# CarTalkImu.net
KiCad netlist of a schematic drawn in EAGLE
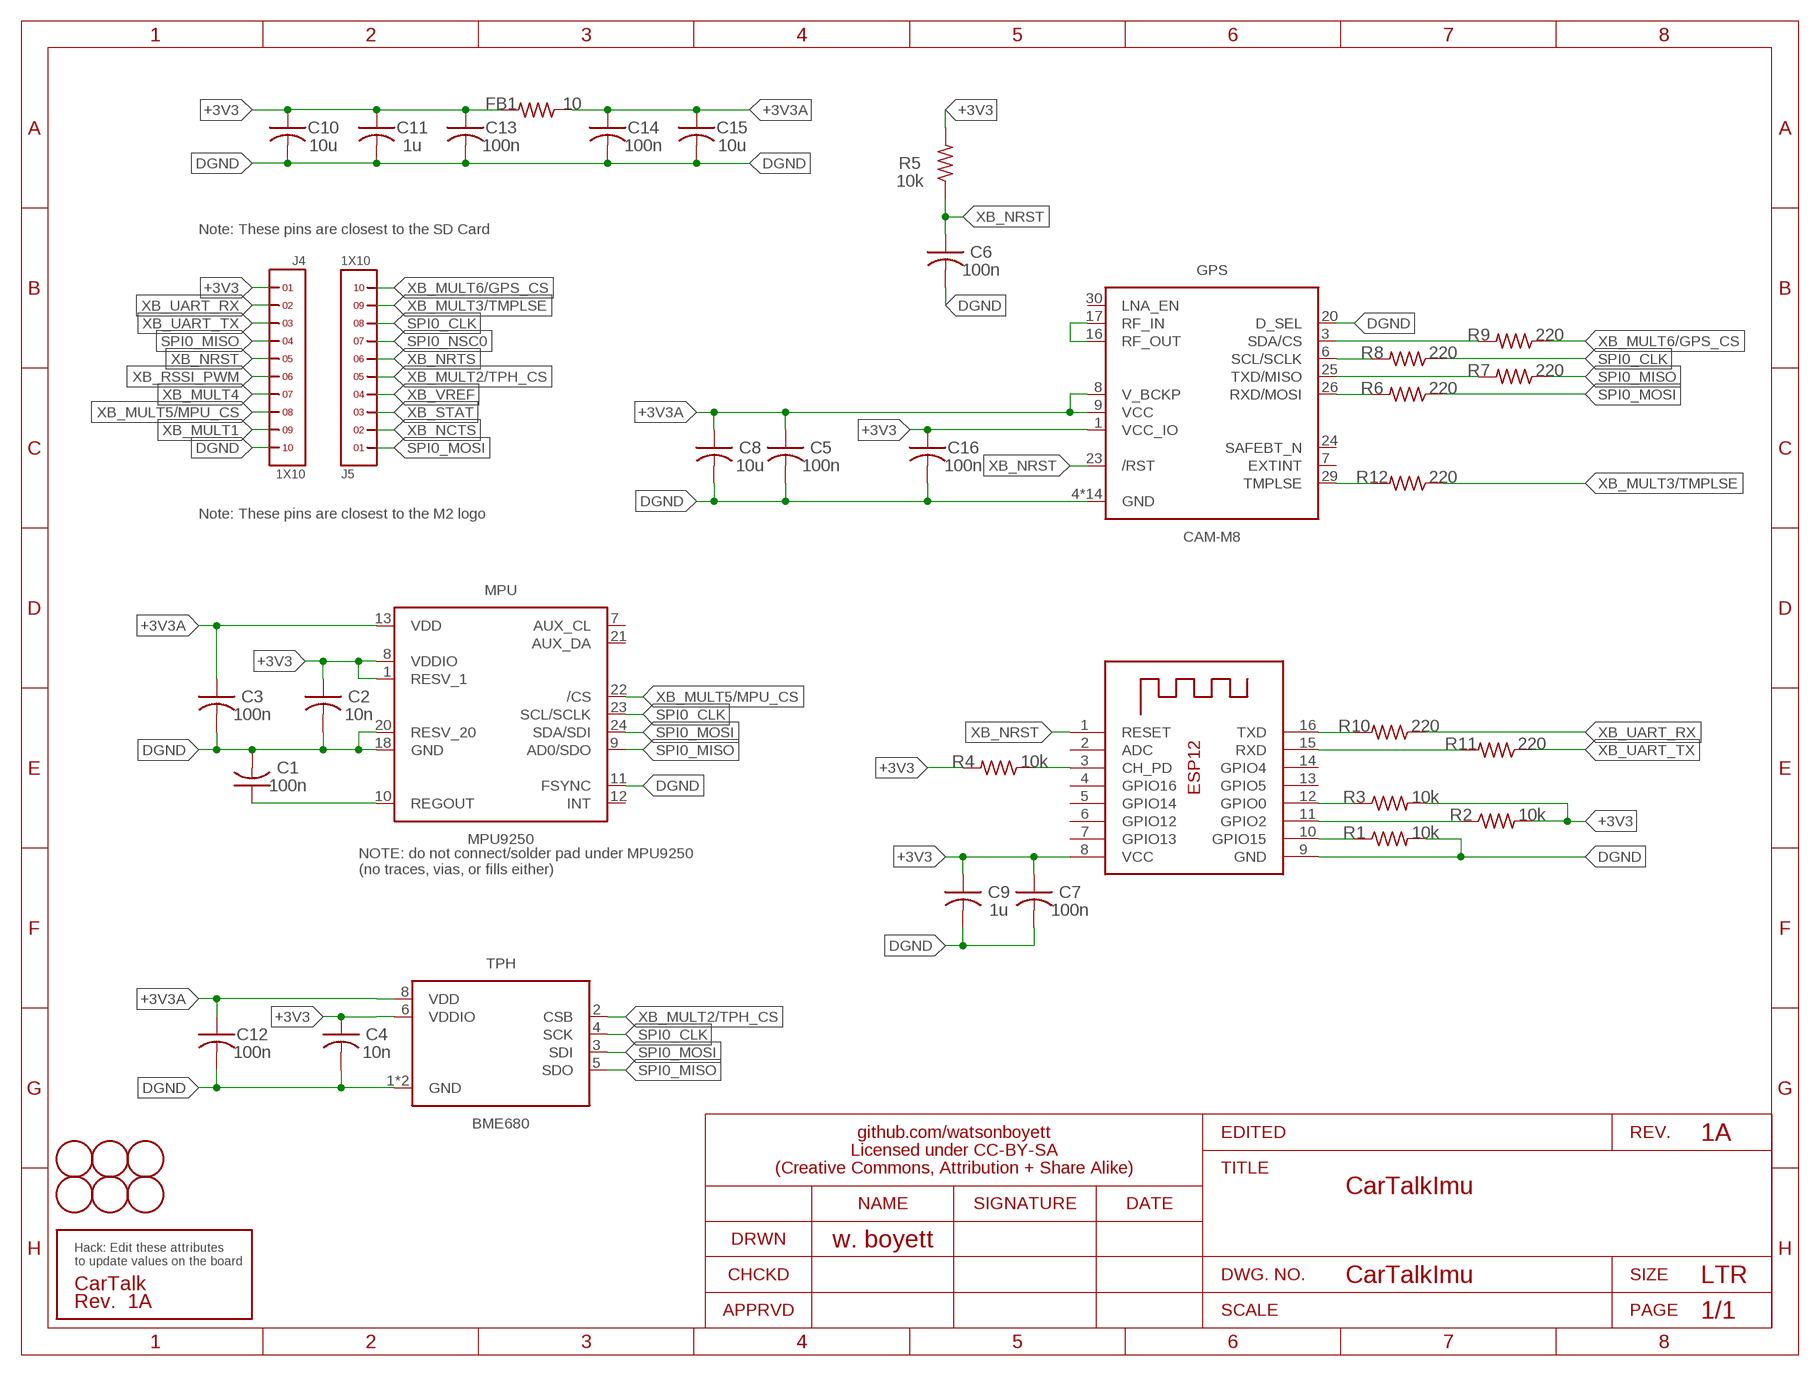
[diagram p0: schematic, sheet 1]

(export (version "E")
  (design (tool "Eeschema 10.0.6"))
  (components
    (comp (ref "C1")
      (value "100n")
      (footprint "eagle-import:C0603")
      (libsource (lib "eagle-import") (part "C-USC0603"))
    )
    (comp (ref "C2")
      (value "10n")
      (footprint "eagle-import:C0603")
      (libsource (lib "eagle-import") (part "C-USC0603"))
    )
    (comp (ref "C3")
      (value "100n")
      (footprint "eagle-import:C0603")
      (libsource (lib "eagle-import") (part "C-USC0603"))
    )
    (comp (ref "C4")
      (value "10n")
      (footprint "eagle-import:C0603")
      (libsource (lib "eagle-import") (part "C-USC0603"))
    )
    (comp (ref "C5")
      (value "100n")
      (footprint "eagle-import:C0603")
      (libsource (lib "eagle-import") (part "C-USC0603"))
    )
    (comp (ref "C6")
      (value "100n")
      (footprint "eagle-import:C0603")
      (libsource (lib "eagle-import") (part "C-USC0603"))
    )
    (comp (ref "C7")
      (value "100n")
      (footprint "eagle-import:C0603")
      (libsource (lib "eagle-import") (part "C-USC0603"))
    )
    (comp (ref "C8")
      (value "10u")
      (footprint "eagle-import:C0805")
      (libsource (lib "eagle-import") (part "C-USC0805"))
    )
    (comp (ref "C9")
      (value "1u")
      (footprint "eagle-import:C0603")
      (libsource (lib "eagle-import") (part "C-USC0603"))
    )
    (comp (ref "C10")
      (value "10u")
      (footprint "eagle-import:C0805")
      (libsource (lib "eagle-import") (part "C-USC0805"))
    )
    (comp (ref "C11")
      (value "1u")
      (footprint "eagle-import:C0603")
      (libsource (lib "eagle-import") (part "C-USC0603"))
    )
    (comp (ref "C12")
      (value "100n")
      (footprint "eagle-import:C0603")
      (libsource (lib "eagle-import") (part "C-USC0603"))
    )
    (comp (ref "C13")
      (value "100n")
      (footprint "eagle-import:C0603")
      (libsource (lib "eagle-import") (part "C-USC0603"))
    )
    (comp (ref "C14")
      (value "100n")
      (footprint "eagle-import:C0603")
      (libsource (lib "eagle-import") (part "C-USC0603"))
    )
    (comp (ref "C15")
      (value "10u")
      (footprint "eagle-import:C0805")
      (libsource (lib "eagle-import") (part "C-USC0805"))
    )
    (comp (ref "C16")
      (value "100n")
      (footprint "eagle-import:C0603")
      (libsource (lib "eagle-import") (part "C-USC0603"))
    )
    (comp (ref "FB1")
      (value "10")
      (footprint "eagle-import:R0603")
      (libsource (lib "eagle-import") (part "R-US_R0603"))
    )
    (comp (ref "GPS")
      (value "CAM-M8")
      (footprint "eagle-import:CAM-M8")
      (fields (field (name "MFG") "U-Blox America Inc.") (field (name "MPN") "CAM-M8Q-0"))
      (libsource (lib "eagle-import") (part "CAM-M8"))
    )
    (comp (ref "J4")
      (value "1X10")
      (footprint "eagle-import:1X10")
      (libsource (lib "eagle-import") (part "1X10"))
    )
    (comp (ref "J5")
      (value "1X10")
      (footprint "eagle-import:1X10")
      (libsource (lib "eagle-import") (part "1X10"))
    )
    (comp (ref "MPU")
      (value "MPU9250")
      (footprint "eagle-import:QFN24-NP")
      (fields (field (name "MFG") "TDK InvenSense") (field (name "MPN") "MPU-9250"))
      (libsource (lib "eagle-import") (part "MPU9250"))
    )
    (comp (ref "R1")
      (value "10k")
      (footprint "eagle-import:R0603")
      (libsource (lib "eagle-import") (part "R-US_R0603"))
    )
    (comp (ref "R2")
      (value "10k")
      (footprint "eagle-import:R0603")
      (libsource (lib "eagle-import") (part "R-US_R0603"))
    )
    (comp (ref "R3")
      (value "10k")
      (footprint "eagle-import:R0603")
      (libsource (lib "eagle-import") (part "R-US_R0603"))
    )
    (comp (ref "R4")
      (value "10k")
      (footprint "eagle-import:R0603")
      (libsource (lib "eagle-import") (part "R-US_R0603"))
    )
    (comp (ref "R5")
      (value "10k")
      (footprint "eagle-import:R0603")
      (libsource (lib "eagle-import") (part "R-US_R0603"))
    )
    (comp (ref "R6")
      (value "220")
      (footprint "eagle-import:R0603")
      (libsource (lib "eagle-import") (part "R-US_R0603"))
    )
    (comp (ref "R7")
      (value "220")
      (footprint "eagle-import:R0603")
      (libsource (lib "eagle-import") (part "R-US_R0603"))
    )
    (comp (ref "R8")
      (value "220")
      (footprint "eagle-import:R0603")
      (libsource (lib "eagle-import") (part "R-US_R0603"))
    )
    (comp (ref "R9")
      (value "220")
      (footprint "eagle-import:R0603")
      (libsource (lib "eagle-import") (part "R-US_R0603"))
    )
    (comp (ref "R10")
      (value "220")
      (footprint "eagle-import:R0603")
      (libsource (lib "eagle-import") (part "R-US_R0603"))
    )
    (comp (ref "R11")
      (value "220")
      (footprint "eagle-import:R0603")
      (libsource (lib "eagle-import") (part "R-US_R0603"))
    )
    (comp (ref "R12")
      (value "220")
      (footprint "eagle-import:R0603")
      (libsource (lib "eagle-import") (part "R-US_R0603"))
    )
    (comp (ref "TPH")
      (value "BME680")
      (footprint "eagle-import:BME-DFN8")
      (fields (field (name "MFG") "Bosch Sensortec"))
      (libsource (lib "eagle-import") (part "BME680"))
    )
    (comp (ref "U$5")
      (value "SILK_QC")
      (footprint "eagle-import:SILK_QC")
      (fields (field (name "MPN") "DNP") (field (name "PRODUCT") "CarTalk") (field (name "REV") "1A"))
      (libsource (lib "eagle-import") (part "SILK_QC"))
    )
    (comp (ref "U$6")
      (value "FIDUCIAL")
      (footprint "eagle-import:FIDUCIAL_1MM")
      (fields (field (name "MPN") "DNP"))
      (libsource (lib "eagle-import") (part "FIDUCIAL"))
    )
    (comp (ref "U$7")
      (value "FIDUCIAL")
      (footprint "eagle-import:FIDUCIAL_1MM")
      (fields (field (name "MPN") "DNP"))
      (libsource (lib "eagle-import") (part "FIDUCIAL"))
    )
    (comp (ref "U$8")
      (value "FIDUCIAL")
      (footprint "eagle-import:FIDUCIAL_1MM")
      (fields (field (name "MPN") "DNP"))
      (libsource (lib "eagle-import") (part "FIDUCIAL"))
    )
    (comp (ref "U$9")
      (value "FIDUCIAL")
      (footprint "eagle-import:FIDUCIAL_1MM")
      (fields (field (name "MPN") "DNP"))
      (libsource (lib "eagle-import") (part "FIDUCIAL"))
    )
    (comp (ref "U$10")
      (value "FIDUCIAL")
      (footprint "eagle-import:FIDUCIAL_1MM")
      (fields (field (name "MPN") "DNP"))
      (libsource (lib "eagle-import") (part "FIDUCIAL"))
    )
    (comp (ref "U$11")
      (value "FIDUCIAL")
      (footprint "eagle-import:FIDUCIAL_1MM")
      (fields (field (name "MPN") "DNP"))
      (libsource (lib "eagle-import") (part "FIDUCIAL"))
    )
    (comp (ref "WIFI")
      (value "ESP-12")
      (footprint "eagle-import:ESP-12")
      (libsource (lib "eagle-import") (part "ESP-12"))
    )
  )
  (nets
    (net (code "1") (name "+3V3") (class "Default")
      (node (ref "C10") (pin "1") (pinfunction "1_1") (pintype "passive"))
      (node (ref "C11") (pin "1") (pinfunction "1_1") (pintype "passive"))
      (node (ref "C13") (pin "1") (pinfunction "1_1") (pintype "passive"))
      (node (ref "C16") (pin "1") (pinfunction "1_1") (pintype "passive"))
      (node (ref "C2") (pin "1") (pinfunction "1_1") (pintype "passive"))
      (node (ref "C4") (pin "1") (pinfunction "1_1") (pintype "passive"))
      (node (ref "C7") (pin "1") (pinfunction "1_1") (pintype "passive"))
      (node (ref "C9") (pin "1") (pinfunction "1_1") (pintype "passive"))
      (node (ref "FB1") (pin "2") (pinfunction "2_2") (pintype "passive"))
      (node (ref "GPS") (pin "1") (pinfunction "VCC_IO_1") (pintype "bidirectional"))
      (node (ref "J4") (pin "1") (pinfunction "1_1") (pintype "bidirectional"))
      (node (ref "MPU") (pin "1") (pinfunction "RESV_1_1") (pintype "bidirectional"))
      (node (ref "MPU") (pin "8") (pinfunction "VDDIO_8") (pintype "bidirectional"))
      (node (ref "R1") (pin "2") (pinfunction "2_2") (pintype "passive"))
      (node (ref "R2") (pin "2") (pinfunction "2_2") (pintype "passive"))
      (node (ref "R4") (pin "2") (pinfunction "2_2") (pintype "passive"))
      (node (ref "R5") (pin "2") (pinfunction "2_2") (pintype "passive"))
      (node (ref "TPH") (pin "6") (pinfunction "VDDIO_6") (pintype "bidirectional"))
      (node (ref "WIFI") (pin "8") (pinfunction "VCC_8") (pintype "power_in"))
    )
    (net (code "2") (name "+3V3A") (class "Default")
      (node (ref "C12") (pin "1") (pinfunction "1_1") (pintype "passive"))
      (node (ref "C14") (pin "1") (pinfunction "1_1") (pintype "passive"))
      (node (ref "C15") (pin "1") (pinfunction "1_1") (pintype "passive"))
      (node (ref "C3") (pin "1") (pinfunction "1_1") (pintype "passive"))
      (node (ref "C5") (pin "1") (pinfunction "1_1") (pintype "passive"))
      (node (ref "C8") (pin "1") (pinfunction "1_1") (pintype "passive"))
      (node (ref "FB1") (pin "1") (pinfunction "1_1") (pintype "passive"))
      (node (ref "GPS") (pin "8") (pinfunction "V_BCKP_8") (pintype "bidirectional"))
      (node (ref "GPS") (pin "9") (pinfunction "VCC_9") (pintype "bidirectional"))
      (node (ref "MPU") (pin "13") (pinfunction "VDD_13") (pintype "bidirectional"))
      (node (ref "TPH") (pin "8") (pinfunction "VDD_8") (pintype "bidirectional"))
    )
    (net (code "3") (name "DGND") (class "Default")
      (node (ref "C1") (pin "2") (pinfunction "2_2") (pintype "passive"))
      (node (ref "C10") (pin "2") (pinfunction "2_2") (pintype "passive"))
      (node (ref "C11") (pin "2") (pinfunction "2_2") (pintype "passive"))
      (node (ref "C12") (pin "2") (pinfunction "2_2") (pintype "passive"))
      (node (ref "C13") (pin "2") (pinfunction "2_2") (pintype "passive"))
      (node (ref "C14") (pin "2") (pinfunction "2_2") (pintype "passive"))
      (node (ref "C15") (pin "2") (pinfunction "2_2") (pintype "passive"))
      (node (ref "C16") (pin "2") (pinfunction "2_2") (pintype "passive"))
      (node (ref "C2") (pin "2") (pinfunction "2_2") (pintype "passive"))
      (node (ref "C3") (pin "2") (pinfunction "2_2") (pintype "passive"))
      (node (ref "C4") (pin "2") (pinfunction "2_2") (pintype "passive"))
      (node (ref "C5") (pin "2") (pinfunction "2_2") (pintype "passive"))
      (node (ref "C6") (pin "2") (pinfunction "2_2") (pintype "passive"))
      (node (ref "C7") (pin "2") (pinfunction "2_2") (pintype "passive"))
      (node (ref "C8") (pin "2") (pinfunction "2_2") (pintype "passive"))
      (node (ref "C9") (pin "2") (pinfunction "2_2") (pintype "passive"))
      (node (ref "GPS") (pin "10") (pinfunction "GND_10") (pintype "bidirectional"))
      (node (ref "GPS") (pin "11") (pinfunction "GND_11") (pintype "bidirectional"))
      (node (ref "GPS") (pin "12") (pinfunction "GND_12") (pintype "bidirectional"))
      (node (ref "GPS") (pin "13") (pinfunction "GND_13") (pintype "bidirectional"))
      (node (ref "GPS") (pin "14") (pinfunction "GND_14") (pintype "bidirectional"))
      (node (ref "GPS") (pin "15") (pinfunction "GND_15") (pintype "bidirectional"))
      (node (ref "GPS") (pin "18") (pinfunction "GND_18") (pintype "bidirectional"))
      (node (ref "GPS") (pin "19") (pinfunction "GND_19") (pintype "bidirectional"))
      (node (ref "GPS") (pin "20") (pinfunction "D_SEL_20") (pintype "bidirectional"))
      (node (ref "GPS") (pin "21") (pinfunction "GND_21") (pintype "bidirectional"))
      (node (ref "GPS") (pin "22") (pinfunction "GND_22") (pintype "bidirectional"))
      (node (ref "GPS") (pin "27") (pinfunction "GND_27") (pintype "bidirectional"))
      (node (ref "GPS") (pin "31") (pinfunction "GND_31") (pintype "bidirectional"))
      (node (ref "GPS") (pin "4") (pinfunction "GND_4") (pintype "bidirectional"))
      (node (ref "GPS") (pin "5") (pinfunction "GND_5") (pintype "bidirectional"))
      (node (ref "J4") (pin "10") (pinfunction "10_10") (pintype "bidirectional"))
      (node (ref "MPU") (pin "11") (pinfunction "FSYNC_11") (pintype "bidirectional"))
      (node (ref "MPU") (pin "18") (pinfunction "GND_18") (pintype "bidirectional"))
      (node (ref "MPU") (pin "20") (pinfunction "RESV_20_20") (pintype "bidirectional"))
      (node (ref "R3") (pin "2") (pinfunction "2_2") (pintype "passive"))
      (node (ref "TPH") (pin "1") (pinfunction "GND_1") (pintype "bidirectional"))
      (node (ref "TPH") (pin "7") (pinfunction "GND_7") (pintype "bidirectional"))
      (node (ref "WIFI") (pin "9") (pinfunction "GND_9") (pintype "power_in"))
    )
    (net (code "4") (name "Net-(GPS-RF_IN)") (class "Default")
      (node (ref "GPS") (pin "16") (pinfunction "RF_OUT_16") (pintype "bidirectional"))
      (node (ref "GPS") (pin "17") (pinfunction "RF_IN_17") (pintype "bidirectional"))
    )
    (net (code "5") (name "Net-(GPS-RXD{slash}MOSI)") (class "Default")
      (node (ref "GPS") (pin "26") (pinfunction "RXD/MOSI_26") (pintype "bidirectional"))
      (node (ref "R6") (pin "2") (pinfunction "2_2") (pintype "passive"))
    )
    (net (code "6") (name "Net-(GPS-SCL{slash}SCLK)") (class "Default")
      (node (ref "GPS") (pin "6") (pinfunction "SCL/SCLK_6") (pintype "bidirectional"))
      (node (ref "R8") (pin "2") (pinfunction "2_2") (pintype "passive"))
    )
    (net (code "7") (name "Net-(GPS-SDA{slash}CS)") (class "Default")
      (node (ref "GPS") (pin "3") (pinfunction "SDA/CS_3") (pintype "bidirectional"))
      (node (ref "R9") (pin "2") (pinfunction "2_2") (pintype "passive"))
    )
    (net (code "8") (name "Net-(GPS-TMPLSE)") (class "Default")
      (node (ref "GPS") (pin "29") (pinfunction "TMPLSE_29") (pintype "bidirectional"))
      (node (ref "R12") (pin "2") (pinfunction "2_2") (pintype "passive"))
    )
    (net (code "9") (name "Net-(GPS-TXD{slash}MISO)") (class "Default")
      (node (ref "GPS") (pin "25") (pinfunction "TXD/MISO_25") (pintype "bidirectional"))
      (node (ref "R7") (pin "2") (pinfunction "2_2") (pintype "passive"))
    )
    (net (code "10") (name "Net-(MPU-REGOUT)") (class "Default")
      (node (ref "C1") (pin "1") (pinfunction "1_1") (pintype "passive"))
      (node (ref "MPU") (pin "10") (pinfunction "REGOUT_10") (pintype "bidirectional"))
    )
    (net (code "11") (name "Net-(WIFI-CH_PD)") (class "Default")
      (node (ref "R4") (pin "1") (pinfunction "1_1") (pintype "passive"))
      (node (ref "WIFI") (pin "3") (pinfunction "CH_PD_3") (pintype "input"))
    )
    (net (code "12") (name "Net-(WIFI-GPIO0)") (class "Default")
      (node (ref "R1") (pin "1") (pinfunction "1_1") (pintype "passive"))
      (node (ref "WIFI") (pin "12") (pinfunction "GPIO0_12") (pintype "bidirectional"))
    )
    (net (code "13") (name "Net-(WIFI-GPIO2)") (class "Default")
      (node (ref "R2") (pin "1") (pinfunction "1_1") (pintype "passive"))
      (node (ref "WIFI") (pin "11") (pinfunction "GPIO2_11") (pintype "bidirectional"))
    )
    (net (code "14") (name "Net-(WIFI-GPIO15)") (class "Default")
      (node (ref "R3") (pin "1") (pinfunction "1_1") (pintype "passive"))
      (node (ref "WIFI") (pin "10") (pinfunction "GPIO15_10") (pintype "bidirectional"))
    )
    (net (code "15") (name "Net-(WIFI-RXD)") (class "Default")
      (node (ref "R11") (pin "2") (pinfunction "2_2") (pintype "passive"))
      (node (ref "WIFI") (pin "15") (pinfunction "RXD_15") (pintype "input"))
    )
    (net (code "16") (name "Net-(WIFI-TXD)") (class "Default")
      (node (ref "R10") (pin "2") (pinfunction "2_2") (pintype "passive"))
      (node (ref "WIFI") (pin "16") (pinfunction "TXD_16") (pintype "output"))
    )
    (net (code "17") (name "SPI0_CLK") (class "Default")
      (node (ref "J5") (pin "8") (pinfunction "8_8") (pintype "bidirectional"))
      (node (ref "MPU") (pin "23") (pinfunction "SCL/SCLK_23") (pintype "bidirectional"))
      (node (ref "R8") (pin "1") (pinfunction "1_1") (pintype "passive"))
      (node (ref "TPH") (pin "4") (pinfunction "SCK_4") (pintype "bidirectional"))
    )
    (net (code "18") (name "SPI0_MISO") (class "Default")
      (node (ref "J4") (pin "4") (pinfunction "4_4") (pintype "bidirectional"))
      (node (ref "MPU") (pin "9") (pinfunction "AD0/SDO_9") (pintype "bidirectional"))
      (node (ref "R7") (pin "1") (pinfunction "1_1") (pintype "passive"))
      (node (ref "TPH") (pin "5") (pinfunction "SDO_5") (pintype "bidirectional"))
    )
    (net (code "19") (name "SPI0_MOSI") (class "Default")
      (node (ref "J5") (pin "1") (pinfunction "1_1") (pintype "bidirectional"))
      (node (ref "MPU") (pin "24") (pinfunction "SDA/SDI_24") (pintype "bidirectional"))
      (node (ref "R6") (pin "1") (pinfunction "1_1") (pintype "passive"))
      (node (ref "TPH") (pin "3") (pinfunction "SDI_3") (pintype "bidirectional"))
    )
    (net (code "20") (name "SPI0_NSC0") (class "Default")
      (node (ref "J5") (pin "7") (pinfunction "7_7") (pintype "bidirectional"))
    )
    (net (code "21") (name "XB_MULT1") (class "Default")
      (node (ref "J4") (pin "9") (pinfunction "9_9") (pintype "bidirectional"))
    )
    (net (code "22") (name "XB_MULT2{slash}TPH_CS") (class "Default")
      (node (ref "J5") (pin "5") (pinfunction "5_5") (pintype "bidirectional"))
      (node (ref "TPH") (pin "2") (pinfunction "CSB_2") (pintype "bidirectional"))
    )
    (net (code "23") (name "XB_MULT3{slash}TMPLSE") (class "Default")
      (node (ref "J5") (pin "9") (pinfunction "9_9") (pintype "bidirectional"))
      (node (ref "R12") (pin "1") (pinfunction "1_1") (pintype "passive"))
    )
    (net (code "24") (name "XB_MULT4") (class "Default")
      (node (ref "J4") (pin "7") (pinfunction "7_7") (pintype "bidirectional"))
    )
    (net (code "25") (name "XB_MULT5{slash}MPU_CS") (class "Default")
      (node (ref "J4") (pin "8") (pinfunction "8_8") (pintype "bidirectional"))
      (node (ref "MPU") (pin "22") (pinfunction "/CS_22") (pintype "bidirectional"))
    )
    (net (code "26") (name "XB_MULT6{slash}GPS_CS") (class "Default")
      (node (ref "J5") (pin "10") (pinfunction "10_10") (pintype "bidirectional"))
      (node (ref "R9") (pin "1") (pinfunction "1_1") (pintype "passive"))
    )
    (net (code "27") (name "XB_NCTS") (class "Default")
      (node (ref "J5") (pin "2") (pinfunction "2_2") (pintype "bidirectional"))
    )
    (net (code "28") (name "XB_NRST") (class "Default")
      (node (ref "C6") (pin "1") (pinfunction "1_1") (pintype "passive"))
      (node (ref "GPS") (pin "23") (pinfunction "/RST_23") (pintype "bidirectional"))
      (node (ref "J4") (pin "5") (pinfunction "5_5") (pintype "bidirectional"))
      (node (ref "R5") (pin "1") (pinfunction "1_1") (pintype "passive"))
      (node (ref "WIFI") (pin "1") (pinfunction "RESET_1") (pintype "input"))
    )
    (net (code "29") (name "XB_NRTS") (class "Default")
      (node (ref "J5") (pin "6") (pinfunction "6_6") (pintype "bidirectional"))
    )
    (net (code "30") (name "XB_RSSI_PWM") (class "Default")
      (node (ref "J4") (pin "6") (pinfunction "6_6") (pintype "bidirectional"))
    )
    (net (code "31") (name "XB_STAT") (class "Default")
      (node (ref "J5") (pin "3") (pinfunction "3_3") (pintype "bidirectional"))
    )
    (net (code "32") (name "XB_UART_RX") (class "Default")
      (node (ref "J4") (pin "2") (pinfunction "2_2") (pintype "bidirectional"))
      (node (ref "R10") (pin "1") (pinfunction "1_1") (pintype "passive"))
    )
    (net (code "33") (name "XB_UART_TX") (class "Default")
      (node (ref "J4") (pin "3") (pinfunction "3_3") (pintype "bidirectional"))
      (node (ref "R11") (pin "1") (pinfunction "1_1") (pintype "passive"))
    )
    (net (code "34") (name "XB_VREF") (class "Default")
      (node (ref "J5") (pin "4") (pinfunction "4_4") (pintype "bidirectional"))
    )
    (net (code "35") (name "unconnected-(GPS-EXTINT-Pad7)") (class "Default")
      (node (ref "GPS") (pin "7") (pinfunction "EXTINT_7") (pintype "bidirectional"))
    )
    (net (code "36") (name "unconnected-(GPS-LNA_EN-Pad30)") (class "Default")
      (node (ref "GPS") (pin "30") (pinfunction "LNA_EN_30") (pintype "bidirectional"))
    )
    (net (code "37") (name "unconnected-(GPS-SAFEBT_N-Pad24)") (class "Default")
      (node (ref "GPS") (pin "24") (pinfunction "SAFEBT_N_24") (pintype "bidirectional"))
    )
    (net (code "38") (name "unconnected-(MPU-AUX_CL-Pad7)") (class "Default")
      (node (ref "MPU") (pin "7") (pinfunction "AUX_CL_7") (pintype "bidirectional"))
    )
    (net (code "39") (name "unconnected-(MPU-AUX_DA-Pad21)") (class "Default")
      (node (ref "MPU") (pin "21") (pinfunction "AUX_DA_21") (pintype "bidirectional"))
    )
    (net (code "40") (name "unconnected-(MPU-INT-Pad12)") (class "Default")
      (node (ref "MPU") (pin "12") (pinfunction "INT_12") (pintype "bidirectional"))
    )
    (net (code "41") (name "unconnected-(WIFI-ADC-Pad2)") (class "Default")
      (node (ref "WIFI") (pin "2") (pinfunction "ADC_2") (pintype "passive"))
    )
    (net (code "42") (name "unconnected-(WIFI-GPIO4-Pad14)") (class "Default")
      (node (ref "WIFI") (pin "14") (pinfunction "GPIO4_14") (pintype "bidirectional"))
    )
    (net (code "43") (name "unconnected-(WIFI-GPIO5-Pad13)") (class "Default")
      (node (ref "WIFI") (pin "13") (pinfunction "GPIO5_13") (pintype "bidirectional"))
    )
    (net (code "44") (name "unconnected-(WIFI-GPIO12-Pad6)") (class "Default")
      (node (ref "WIFI") (pin "6") (pinfunction "GPIO12_6") (pintype "bidirectional"))
    )
    (net (code "45") (name "unconnected-(WIFI-GPIO13-Pad7)") (class "Default")
      (node (ref "WIFI") (pin "7") (pinfunction "GPIO13_7") (pintype "bidirectional"))
    )
    (net (code "46") (name "unconnected-(WIFI-GPIO14-Pad5)") (class "Default")
      (node (ref "WIFI") (pin "5") (pinfunction "GPIO14_5") (pintype "bidirectional"))
    )
    (net (code "47") (name "unconnected-(WIFI-GPIO16-Pad4)") (class "Default")
      (node (ref "WIFI") (pin "4") (pinfunction "GPIO16_4") (pintype "bidirectional"))
    )
  )
)
